# PDB.net
KiCad netlist of a schematic drawn in Altium Designer
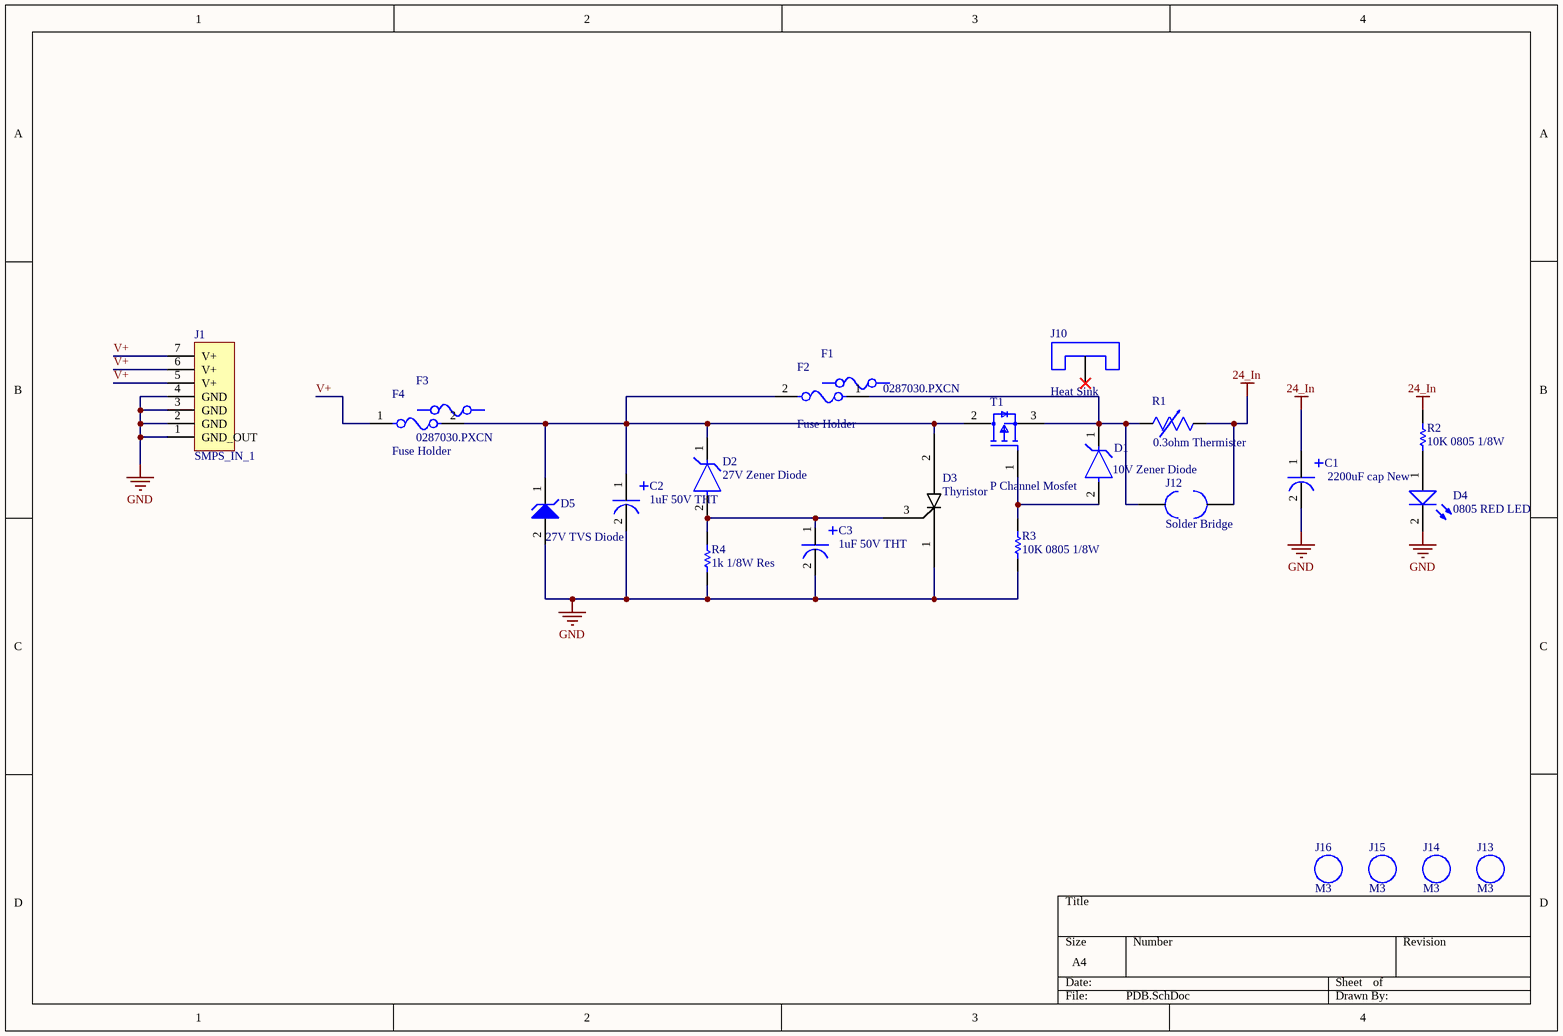
[diagram p0: PDB.SchDoc]

(export (version "E")
  (design (tool "Eeschema 10.0.6"))
  (components
    (comp (ref "C1")
      (value "2200uF cap New")
      (footprint "Capacitor through hole")
      (description "Radial Can ALUMINUM ELECTROLYTIC CAPACITOR 148RUS 50V 2200muF ±20% 0.630Dia 16.00mm")
      (fields
        (field (name "MANUFACTURER") "Vishay")
        (field (name "MANUFACTURER PART NUMBER") "MAL214851222E3")
      )
      (libsource (lib "Schlib1") (part "MAL214851222E3"))
    )
    (comp (ref "C2")
      (value "1uF 50V THT")
      (footprint "capacitor Through Hole Small")
      (description "1uF 50V ±20% Plugin, D5xL11mm Aluminum Electrolytic Capacitors - Leaded ROHS")
      (fields
        (field (name "MANUFACTURER") "Rubycon")
        (field (name "MANUFACTURER PART NUMBER") "50YXF1MEFC5X11")
      )
      (libsource (lib "Schlib1") (part "50YXF1MEFC5X11"))
    )
    (comp (ref "C3")
      (value "1uF 50V THT")
      (footprint "capacitor Through Hole Small")
      (description "1uF 50V ±20% Plugin, D5xL11mm Aluminum Electrolytic Capacitors - Leaded ROHS")
      (fields
        (field (name "MANUFACTURER") "Rubycon")
        (field (name "MANUFACTURER PART NUMBER") "50YXF1MEFC5X11")
      )
      (libsource (lib "Schlib1") (part "50YXF1MEFC5X11"))
    )
    (comp (ref "D1")
      (value "10V Zener Diode")
      (footprint "27V Zener diode")
      (description "Zener Diode Independent 10V 5W Surface Mount SMB(DO-214AA")
      (fields (field (name "MANUFACTURER") "MCC") (field (name "MANUFACTURER PART NUMBER") "3SMBJ5925B-TP"))
      (libsource (lib "Schlib1") (part "SMBJ5347B-TP"))
    )
    (comp (ref "D2")
      (value "27V Zener Diode")
      (footprint "27V Zener diode")
      (description "Zener Diode, 27V, 5W, Do-214Aa Rohs Compliant: Yes ¦Micro Commercial Components SMBJ5361B-TP")
      (fields (field (name "MANUFACTURER") "MCC") (field (name "MANUFACTURER PART NUMBER") "SMBJ5361B-TP"))
      (libsource (lib "Schlib1") (part "SMBJ5361B-TP"))
    )
    (comp (ref "D3")
      (value "Thyristor")
      (footprint "Thyristor")
      (description "SCR 600 V 40 A Standard Recovery Through Hole TO-220")
      (fields
        (field (name "MANUFACTURER") "STMicroelectronics")
        (field (name "MANUFACTURER PART NUMBER") "TN4015H-6I")
      )
      (libsource (lib "Schlib1") (part "TN4015H-6I"))
    )
    (comp (ref "D4")
      (value "0805 RED LED")
      (footprint "0805 LED")
      (description "Led; Red; 11MCD; 0.061IN.DIA.; SMD; 100MA; 2V Vf; 635NM; 140DEG; SMD; White Diffused; 5V Vr")
      (fields
        (field (name "MANUFACTURER") "Lumex")
        (field (name "MANUFACTURER PART NUMBER") "SML-LXT0805IW-TR")
      )
      (libsource (lib "Schlib1") (part "SML-LXT0805IW-TR"))
    )
    (comp (ref "D5")
      (value "27V TVS Diode")
      (footprint "27V TVS Diode")
      (description "600 Watt SUR40 Transient Voltage Suppressor, 27 V, Unidirectional")
      (fields (field (name "MANUFACTURER") "onsemi") (field (name "MANUFACTURER PART NUMBER") "P6KE27ARLG"))
      (libsource (lib "Schlib1") (part "P6KE27ARLG"))
    )
    (comp (ref "F1")
      (value "0287030.PXCN")
      (footprint "FP-0287-MFG")
      (description "FUSE AUTOMOTIVE 30A 32VDC BLADE")
      (fields
        (field (name "OCTOPART") "https://octopart.com/0287030.pxcn-littelfuse-19644293")
        (field (name "MANUFACTURER") "Littelfuse Inc")
      )
      (libsource (lib "Schlib1") (part "CMP-08605-000065-1"))
    )
    (comp (ref "F2")
      (value "Fuse Holder")
      (footprint "FUSE HOLDER")
      (description "Holder; Fuse; Auto Blade; Mini; 500VAC; 30A; PC Pin Terminal; Nylon 4/6 Holder; Black")
      (fields (field (name "MANUFACTURER") "Keystone") (field (name "MANUFACTURER PART NUMBER") "3568"))
      (libsource (lib "Schlib1") (part "3568"))
    )
    (comp (ref "F3")
      (value "0287030.PXCN")
      (footprint "FP-0287-MFG")
      (description "FUSE AUTOMOTIVE 30A 32VDC BLADE")
      (fields
        (field (name "OCTOPART") "https://octopart.com/0287030.pxcn-littelfuse-19644293")
        (field (name "MANUFACTURER") "Littelfuse Inc")
      )
      (libsource (lib "Schlib1") (part "CMP-08605-000065-1"))
    )
    (comp (ref "F4")
      (value "Fuse Holder")
      (footprint "FUSE HOLDER")
      (description "Holder; Fuse; Auto Blade; Mini; 500VAC; 30A; PC Pin Terminal; Nylon 4/6 Holder; Black")
      (fields (field (name "MANUFACTURER") "Keystone") (field (name "MANUFACTURER PART NUMBER") "3568"))
      (libsource (lib "Schlib1") (part "3568"))
    )
    (comp (ref "J1")
      (value "SMPS_IN_1")
      (footprint "7 LUG PIN HEADER")
      (description "5.08mm Pitch Eurostyle Vertical Fixed Mount PCB Terminal Block, 6 Circuits")
      (fields (field (name "MANUFACTURER") "Molex") (field (name "MANUFACTURER PART NUMBER") "39544-3006"))
      (libsource (lib "Schlib1") (part "Terminal Connectors 6"))
    )
    (comp (ref "J10")
      (value "Heat Sink")
      (footprint "Heat Sink")
      (description "TO-220 Package 13.4 C/W Thermal Resistance Large Radial Fin Heat Sink")
      (fields
        (field (name "MANUFACTURER") "Aavid Thermalloy")
        (field (name "MANUFACTURER PART NUMBER") "513001B02500G")
      )
      (libsource (lib "Schlib1") (part "513001B02500G"))
    )
    (comp (ref "J12")
      (value "Solder Bridge")
      (footprint "1206")
      (libsource (lib "Schlib1") (part "Solder Bridge"))
    )
    (comp (ref "J13") (value "M3") (footprint "M3") (libsource (lib "Schlib1") (part "M3")))
    (comp (ref "J14") (value "M3") (footprint "M3") (libsource (lib "Schlib1") (part "M3")))
    (comp (ref "J15") (value "M3") (footprint "M3") (libsource (lib "Schlib1") (part "M3")))
    (comp (ref "J16") (value "M3") (footprint "M3") (libsource (lib "Schlib1") (part "M3")))
    (comp (ref "R1")
      (value "0.3ohm Thermister")
      (footprint "thermistor")
      (description "NTC Thermistor, 0.3ohm, Through Hole Mount")
      (fields (field (name "MANUFACTURER") "Vishay") (field (name "MANUFACTURER PART NUMBER") "SL320R230"))
      (libsource (lib "Schlib1") (part "SL320R230"))
    )
    (comp (ref "R2")
      (value "10K 0805 1/8W")
      (footprint "0805 1K Resistor")
      (description "Res General Purpose Thick Film 0805 10k Ohm 1% 1/8W ±100ppm/°C Ceramic Paper T/R")
      (fields
        (field (name "MANUFACTURER") "Yageo Group")
        (field (name "MANUFACTURER PART NUMBER") "RC0805FR-0710KL")
      )
      (libsource (lib "Schlib1") (part "RC0805FR-0710KL"))
    )
    (comp (ref "R3")
      (value "10K 0805 1/8W")
      (footprint "0805 1K Resistor")
      (description "Res General Purpose Thick Film 0805 10k Ohm 1% 1/8W ±100ppm/°C Ceramic Paper T/R")
      (fields
        (field (name "MANUFACTURER") "Yageo Group")
        (field (name "MANUFACTURER PART NUMBER") "RC0805FR-0710KL")
      )
      (libsource (lib "Schlib1") (part "RC0805FR-0710KL"))
    )
    (comp (ref "R4")
      (value "1k 1/8W Res")
      (footprint "0805 1K Resistor")
      (description "Yageo RC0805FR-071KL SMD Resistor 0603 1k Ohm ±1% Thick Film")
      (fields
        (field (name "MANUFACTURER") "Yageo Group")
        (field (name "MANUFACTURER PART NUMBER") "RC0805FR-071KL")
      )
      (libsource (lib "Schlib1") (part "RC0805FR-071KL"))
    )
    (comp (ref "T1")
      (value "P Channel Mosfet")
      (footprint "P-Ch Mosfet")
      (description "Transistor MOSFET P-CH 60V 90A 3-Pin (3+Tab) TO-220AB")
      (fields
        (field (name "MANUFACTURER") "Vishay")
        (field (name "MANUFACTURER PART NUMBER") "SUP90P06-09L-E3")
      )
      (libsource (lib "Schlib1") (part "SUP90P06-09L-E3"))
    )
  )
  (nets
    (net (code "1") (name "/V+") (class "Default")
      (node (ref "F4") (pin "1") (pinfunction "1_1") (pintype "passive"))
      (node (ref "J1") (pin "5") (pinfunction "V+_5") (pintype "passive"))
      (node (ref "J1") (pin "6") (pinfunction "V+_6") (pintype "passive"))
      (node (ref "J1") (pin "7") (pinfunction "V+_7") (pintype "passive"))
    )
    (net (code "2") (name "24_In") (class "Default")
      (node (ref "C1") (pin "1") (pinfunction "1_1") (pintype "passive"))
      (node (ref "J12") (pin "2") (pinfunction "2_2") (pintype "passive"))
      (node (ref "R1") (pin "1") (pinfunction "1_1") (pintype "passive"))
      (node (ref "R2") (pin "2") (pinfunction "2_2") (pintype "passive"))
    )
    (net (code "3") (name "GND") (class "Default")
      (node (ref "C1") (pin "2") (pinfunction "2_2") (pintype "passive"))
      (node (ref "C2") (pin "2") (pinfunction "2_2") (pintype "passive"))
      (node (ref "C3") (pin "2") (pinfunction "2_2") (pintype "passive"))
      (node (ref "D3") (pin "1") (pinfunction "1_1") (pintype "passive"))
      (node (ref "D4") (pin "2") (pinfunction "K_2") (pintype "passive"))
      (node (ref "D5") (pin "2") (pinfunction "A_2") (pintype "passive"))
      (node (ref "J1") (pin "1") (pinfunction "GND_OUT_1") (pintype "passive"))
      (node (ref "J1") (pin "2") (pinfunction "GND_2") (pintype "passive"))
      (node (ref "J1") (pin "3") (pinfunction "GND_3") (pintype "passive"))
      (node (ref "J1") (pin "4") (pinfunction "GND_4") (pintype "passive"))
      (node (ref "R3") (pin "1") (pinfunction "1_1") (pintype "passive"))
      (node (ref "R4") (pin "1") (pinfunction "1_1") (pintype "passive"))
    )
    (net (code "4") (name "Net-(D1-A)") (class "Default")
      (node (ref "D1") (pin "2") (pinfunction "A_2") (pintype "passive"))
      (node (ref "R3") (pin "2") (pinfunction "2_2") (pintype "passive"))
      (node (ref "T1") (pin "1") (pinfunction "G_1") (pintype "passive"))
    )
    (net (code "5") (name "Net-(D1-C)") (class "Default")
      (node (ref "D1") (pin "1") (pinfunction "C_1") (pintype "passive"))
      (node (ref "F2") (pin "1") (pinfunction "1_1") (pintype "passive"))
      (node (ref "J12") (pin "1") (pinfunction "2_1") (pintype "passive"))
      (node (ref "R1") (pin "2") (pinfunction "2_2") (pintype "passive"))
      (node (ref "T1") (pin "3") (pinfunction "S_3") (pintype "passive"))
    )
    (net (code "6") (name "Net-(D2-A)") (class "Default")
      (node (ref "C3") (pin "1") (pinfunction "1_1") (pintype "passive"))
      (node (ref "D2") (pin "2") (pinfunction "A_2") (pintype "passive"))
      (node (ref "D3") (pin "3") (pinfunction "3_3") (pintype "passive"))
      (node (ref "R4") (pin "2") (pinfunction "2_2") (pintype "passive"))
    )
    (net (code "7") (name "Net-(D2-C)") (class "Default")
      (node (ref "C2") (pin "1") (pinfunction "1_1") (pintype "passive"))
      (node (ref "D2") (pin "1") (pinfunction "C_1") (pintype "passive"))
      (node (ref "D3") (pin "2") (pinfunction "2_2") (pintype "passive"))
      (node (ref "D5") (pin "1") (pinfunction "K_1") (pintype "passive"))
      (node (ref "F2") (pin "2") (pinfunction "2_2") (pintype "passive"))
      (node (ref "F4") (pin "2") (pinfunction "2_2") (pintype "passive"))
      (node (ref "T1") (pin "2") (pinfunction "D_2") (pintype "passive"))
    )
    (net (code "8") (name "Net-(D4-A)") (class "Default")
      (node (ref "D4") (pin "1") (pinfunction "A_1") (pintype "passive"))
      (node (ref "R2") (pin "1") (pinfunction "1_1") (pintype "passive"))
    )
    (net (code "9") (name "unconnected-(J10-Pad1)") (class "Default")
      (node (ref "J10") (pin "1") (pinfunction "1_1") (pintype "passive+no_connect"))
    )
  )
)
